# pulser.net
KiCad netlist of a schematic drawn in EAGLE
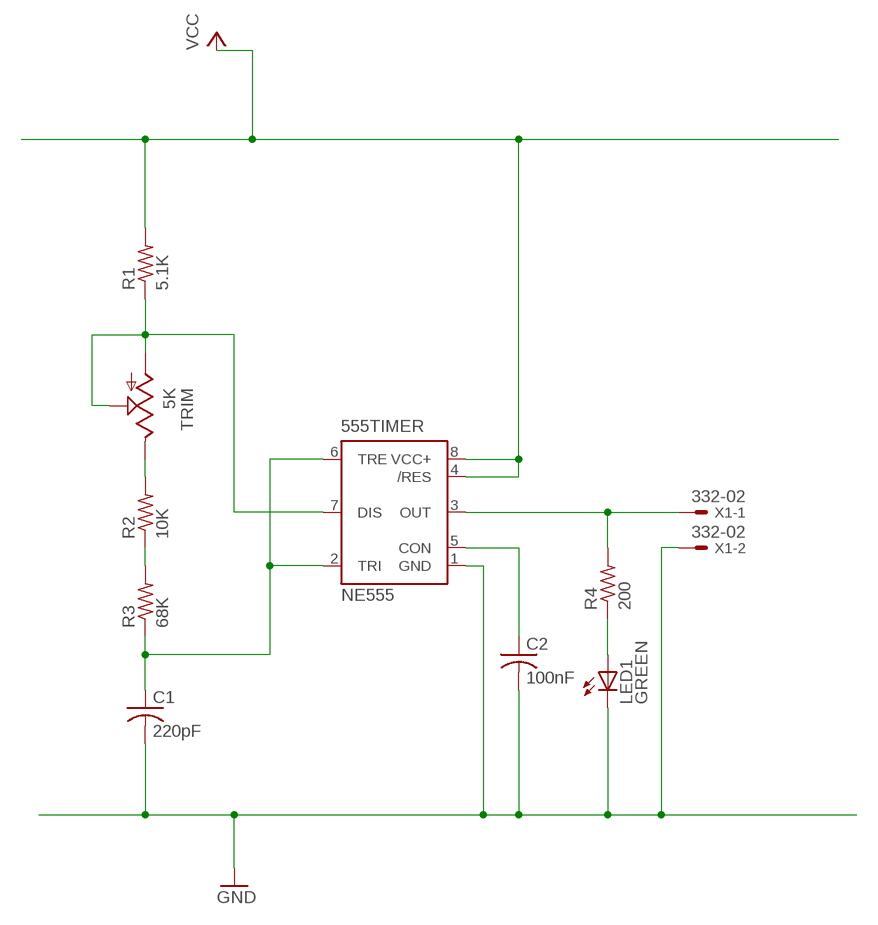
[diagram p0: schematic, sheet 1]

(export (version "E")
  (design (tool "Eeschema 10.0.6"))
  (components
    (comp (ref "555TIMER")
      (value "NE555")
      (footprint "eagle-import:DIL-08")
      (fields (field (name "MF") "Arrow Electronics") (field (name "MPN") "NE555N"))
      (libsource (lib "eagle-import") (part "NE555"))
    )
    (comp (ref "C1")
      (value "220pF")
      (footprint "eagle-import:C025-025X050")
      (libsource (lib "eagle-import") (part "C-US025-025X050"))
    )
    (comp (ref "C2")
      (value "100nF")
      (footprint "eagle-import:C025-024X044")
      (libsource (lib "eagle-import") (part "C-US025-024X044"))
    )
    (comp (ref "LED1")
      (value "GREEN")
      (footprint "eagle-import:LED5MM")
      (libsource (lib "eagle-import") (part "LED5MM"))
    )
    (comp (ref "R1")
      (value "5.1K")
      (footprint "eagle-import:0207_10")
      (libsource (lib "eagle-import") (part "R-US_0207/10"))
    )
    (comp (ref "R2")
      (value "10K")
      (footprint "eagle-import:0207_10")
      (libsource (lib "eagle-import") (part "R-US_0207/10"))
    )
    (comp (ref "R3")
      (value "68K")
      (footprint "eagle-import:0207_10")
      (libsource (lib "eagle-import") (part "R-US_0207/10"))
    )
    (comp (ref "R4")
      (value "200")
      (footprint "eagle-import:0207_10")
      (libsource (lib "eagle-import") (part "R-US_0207/10"))
    )
    (comp (ref "TRIM")
      (value "5K")
      (footprint "eagle-import:S64W")
      (libsource (lib "eagle-import") (part "TRIM_US-S64W"))
    )
    (comp (ref "X1")
      (value "332-02")
      (footprint "eagle-import:332-02")
      (libsource (lib "eagle-import") (part "332-02"))
    )
  )
  (nets
    (net (code "1") (name "GND") (class "Default")
      (node (ref "555TIMER") (pin "1") (pinfunction "GND_1") (pintype "power_in"))
      (node (ref "C1") (pin "2") (pinfunction "2_2") (pintype "passive"))
      (node (ref "C2") (pin "2") (pinfunction "2_2") (pintype "passive"))
      (node (ref "LED1") (pin "K") (pinfunction "C_K") (pintype "passive"))
      (node (ref "X1") (pin "2") (pinfunction "S_2") (pintype "passive"))
    )
    (net (code "2") (name "Net-(555TIMER-CON)") (class "Default")
      (node (ref "555TIMER") (pin "5") (pinfunction "CON_5") (pintype "input"))
      (node (ref "C2") (pin "1") (pinfunction "1_1") (pintype "passive"))
    )
    (net (code "3") (name "Net-(555TIMER-DIS)") (class "Default")
      (node (ref "555TIMER") (pin "7") (pinfunction "DIS_7") (pintype "input"))
      (node (ref "R1") (pin "1") (pinfunction "1_1") (pintype "passive"))
      (node (ref "TRIM") (pin "A") (pinfunction "A_A") (pintype "passive"))
      (node (ref "TRIM") (pin "S") (pinfunction "S_S") (pintype "passive"))
    )
    (net (code "4") (name "Net-(555TIMER-OUT)") (class "Default")
      (node (ref "555TIMER") (pin "3") (pinfunction "OUT_3") (pintype "output"))
      (node (ref "R4") (pin "2") (pinfunction "2_2") (pintype "passive"))
      (node (ref "X1") (pin "1") (pinfunction "S_1") (pintype "passive"))
    )
    (net (code "5") (name "Net-(555TIMER-TRE)") (class "Default")
      (node (ref "555TIMER") (pin "2") (pinfunction "TRI_2") (pintype "input"))
      (node (ref "555TIMER") (pin "6") (pinfunction "TRE_6") (pintype "input"))
      (node (ref "C1") (pin "1") (pinfunction "1_1") (pintype "passive"))
      (node (ref "R3") (pin "1") (pinfunction "1_1") (pintype "passive"))
    )
    (net (code "6") (name "Net-(LED1-PadA)") (class "Default")
      (node (ref "LED1") (pin "A") (pinfunction "A_A") (pintype "passive"))
      (node (ref "R4") (pin "1") (pinfunction "1_1") (pintype "passive"))
    )
    (net (code "7") (name "Net-(R2-Pad1)") (class "Default")
      (node (ref "R2") (pin "1") (pinfunction "1_1") (pintype "passive"))
      (node (ref "R3") (pin "2") (pinfunction "2_2") (pintype "passive"))
    )
    (net (code "8") (name "Net-(R2-Pad2)") (class "Default")
      (node (ref "R2") (pin "2") (pinfunction "2_2") (pintype "passive"))
      (node (ref "TRIM") (pin "E") (pinfunction "E_E") (pintype "passive"))
    )
    (net (code "9") (name "VCC") (class "Default")
      (node (ref "555TIMER") (pin "4") (pinfunction "/RES_4") (pintype "input"))
      (node (ref "555TIMER") (pin "8") (pinfunction "VCC+_8") (pintype "power_in"))
      (node (ref "R1") (pin "2") (pinfunction "2_2") (pintype "passive"))
    )
  )
)
